# MAX31865ATP.net
KiCad netlist of a schematic drawn in Altium Designer
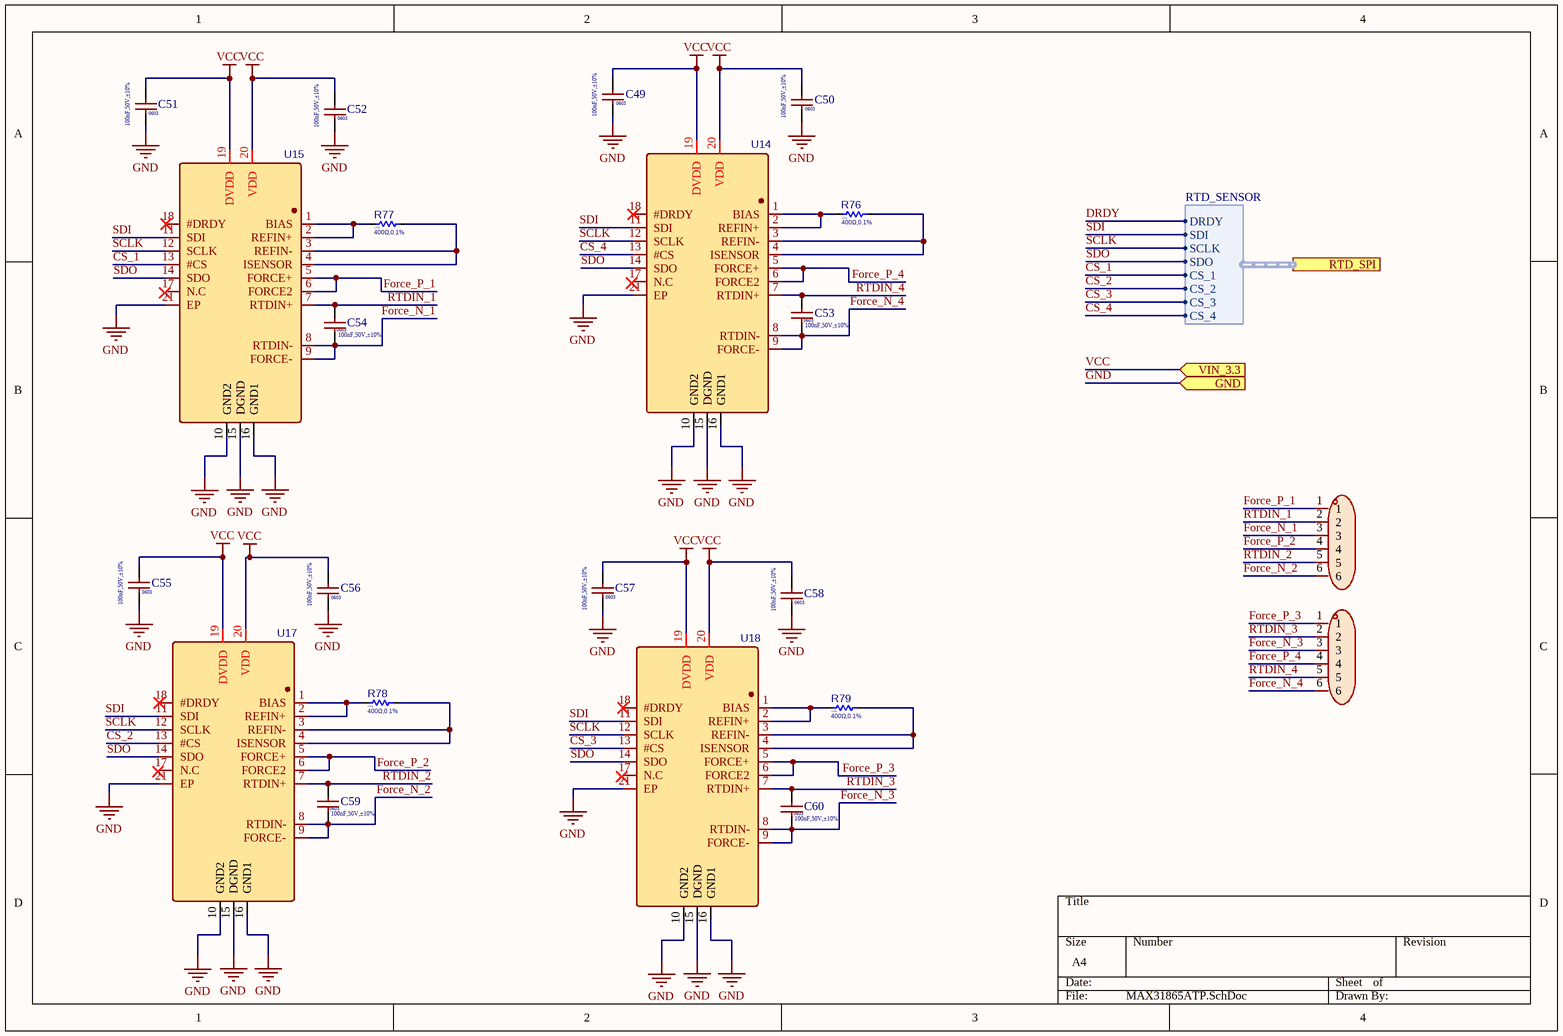
[diagram p0: MAX31865ATP.SchDoc]

(export (version "E")
  (design (tool "Eeschema 10.0.6"))
  (components
    (comp (ref "C49")
      (value "100nF,50V,±10%")
      (footprint "RCL:C0603")
      (description "50V 100nF X7R ±10% 0603 Multilayer Ceramic Capacitors MLCC - SMD/SMT ROHS")
      (fields
        (field (name "MPN") "CL10B104KB8NNNC")
        (field (name "MANUFACTURER") "SAMSUNG")
        (field (name "PACKAGE") "0603")
      )
      (libsource (lib "RCL") (part "CL10B104KB8NNNC"))
    )
    (comp (ref "C50")
      (value "100nF,50V,±10%")
      (footprint "RCL:C0603")
      (description "50V 100nF X7R ±10% 0603 Multilayer Ceramic Capacitors MLCC - SMD/SMT ROHS")
      (fields
        (field (name "MPN") "CL10B104KB8NNNC")
        (field (name "MANUFACTURER") "SAMSUNG")
        (field (name "PACKAGE") "0603")
      )
      (libsource (lib "RCL") (part "CL10B104KB8NNNC"))
    )
    (comp (ref "C51")
      (value "100nF,50V,±10%")
      (footprint "RCL:C0603")
      (description "50V 100nF X7R ±10% 0603 Multilayer Ceramic Capacitors MLCC - SMD/SMT ROHS")
      (fields
        (field (name "MPN") "CL10B104KB8NNNC")
        (field (name "MANUFACTURER") "SAMSUNG")
        (field (name "PACKAGE") "0603")
      )
      (libsource (lib "RCL") (part "CL10B104KB8NNNC"))
    )
    (comp (ref "C52")
      (value "100nF,50V,±10%")
      (footprint "RCL:C0603")
      (description "50V 100nF X7R ±10% 0603 Multilayer Ceramic Capacitors MLCC - SMD/SMT ROHS")
      (fields
        (field (name "MPN") "CL10B104KB8NNNC")
        (field (name "MANUFACTURER") "SAMSUNG")
        (field (name "PACKAGE") "0603")
      )
      (libsource (lib "RCL") (part "CL10B104KB8NNNC"))
    )
    (comp (ref "C53")
      (value "100nF,50V,±10%")
      (footprint "RCL:C0603")
      (description "50V 100nF X7R ±10% 0603 Multilayer Ceramic Capacitors MLCC - SMD/SMT ROHS")
      (fields
        (field (name "MPN") "CL10B104KB8NNNC")
        (field (name "MANUFACTURER") "SAMSUNG")
        (field (name "PACKAGE") "0603")
      )
      (libsource (lib "RCL") (part "CL10B104KB8NNNC"))
    )
    (comp (ref "C54")
      (value "100nF,50V,±10%")
      (footprint "RCL:C0603")
      (description "50V 100nF X7R ±10% 0603 Multilayer Ceramic Capacitors MLCC - SMD/SMT ROHS")
      (fields
        (field (name "MPN") "CL10B104KB8NNNC")
        (field (name "MANUFACTURER") "SAMSUNG")
        (field (name "PACKAGE") "0603")
      )
      (libsource (lib "RCL") (part "CL10B104KB8NNNC"))
    )
    (comp (ref "C55")
      (value "100nF,50V,±10%")
      (footprint "RCL:C0603")
      (description "50V 100nF X7R ±10% 0603 Multilayer Ceramic Capacitors MLCC - SMD/SMT ROHS")
      (fields
        (field (name "MPN") "CL10B104KB8NNNC")
        (field (name "MANUFACTURER") "SAMSUNG")
        (field (name "PACKAGE") "0603")
      )
      (libsource (lib "RCL") (part "CL10B104KB8NNNC"))
    )
    (comp (ref "C56")
      (value "100nF,50V,±10%")
      (footprint "RCL:C0603")
      (description "50V 100nF X7R ±10% 0603 Multilayer Ceramic Capacitors MLCC - SMD/SMT ROHS")
      (fields
        (field (name "MPN") "CL10B104KB8NNNC")
        (field (name "MANUFACTURER") "SAMSUNG")
        (field (name "PACKAGE") "0603")
      )
      (libsource (lib "RCL") (part "CL10B104KB8NNNC"))
    )
    (comp (ref "C57")
      (value "100nF,50V,±10%")
      (footprint "RCL:C0603")
      (description "50V 100nF X7R ±10% 0603 Multilayer Ceramic Capacitors MLCC - SMD/SMT ROHS")
      (fields
        (field (name "MPN") "CL10B104KB8NNNC")
        (field (name "MANUFACTURER") "SAMSUNG")
        (field (name "PACKAGE") "0603")
      )
      (libsource (lib "RCL") (part "CL10B104KB8NNNC"))
    )
    (comp (ref "C58")
      (value "100nF,50V,±10%")
      (footprint "RCL:C0603")
      (description "50V 100nF X7R ±10% 0603 Multilayer Ceramic Capacitors MLCC - SMD/SMT ROHS")
      (fields
        (field (name "MPN") "CL10B104KB8NNNC")
        (field (name "MANUFACTURER") "SAMSUNG")
        (field (name "PACKAGE") "0603")
      )
      (libsource (lib "RCL") (part "CL10B104KB8NNNC"))
    )
    (comp (ref "C59")
      (value "100nF,50V,±10%")
      (footprint "RCL:C0603")
      (description "50V 100nF X7R ±10% 0603 Multilayer Ceramic Capacitors MLCC - SMD/SMT ROHS")
      (fields
        (field (name "MPN") "CL10B104KB8NNNC")
        (field (name "MANUFACTURER") "SAMSUNG")
        (field (name "PACKAGE") "0603")
      )
      (libsource (lib "RCL") (part "CL10B104KB8NNNC"))
    )
    (comp (ref "C60")
      (value "100nF,50V,±10%")
      (footprint "RCL:C0603")
      (description "50V 100nF X7R ±10% 0603 Multilayer Ceramic Capacitors MLCC - SMD/SMT ROHS")
      (fields
        (field (name "MPN") "CL10B104KB8NNNC")
        (field (name "MANUFACTURER") "SAMSUNG")
        (field (name "PACKAGE") "0603")
      )
      (libsource (lib "RCL") (part "CL10B104KB8NNNC"))
    )
    (comp (ref "R76")
      (value "400Ω,0.1%")
      (footprint "R1206")
      (description "250mW Thin Film Resistor 200V ±25ppm/℃ ±0.1% 400Ω 1206 Chip Resistor - Surface Mount ROHS")
      (fields
        (field (name "MANUFACTURER") "YAGEO")
        (field (name "MPN") "RT1206BRD07400RL")
        (field (name "PACKAGE") "1206")
      )
      (libsource (lib "RCL") (part "RT1206BRD07400RL"))
    )
    (comp (ref "R77")
      (value "400Ω,0.1%")
      (footprint "R1206")
      (description "250mW Thin Film Resistor 200V ±25ppm/℃ ±0.1% 400Ω 1206 Chip Resistor - Surface Mount ROHS")
      (fields
        (field (name "MANUFACTURER") "YAGEO")
        (field (name "MPN") "RT1206BRD07400RL")
        (field (name "PACKAGE") "1206")
      )
      (libsource (lib "RCL") (part "RT1206BRD07400RL"))
    )
    (comp (ref "R78")
      (value "400Ω,0.1%")
      (footprint "R1206")
      (description "250mW Thin Film Resistor 200V ±25ppm/℃ ±0.1% 400Ω 1206 Chip Resistor - Surface Mount ROHS")
      (fields
        (field (name "MANUFACTURER") "YAGEO")
        (field (name "MPN") "RT1206BRD07400RL")
        (field (name "PACKAGE") "1206")
      )
      (libsource (lib "RCL") (part "RT1206BRD07400RL"))
    )
    (comp (ref "R79")
      (value "400Ω,0.1%")
      (footprint "R1206")
      (description "250mW Thin Film Resistor 200V ±25ppm/℃ ±0.1% 400Ω 1206 Chip Resistor - Surface Mount ROHS")
      (fields
        (field (name "MANUFACTURER") "YAGEO")
        (field (name "MPN") "RT1206BRD07400RL")
        (field (name "PACKAGE") "1206")
      )
      (libsource (lib "RCL") (part "RT1206BRD07400RL"))
    )
    (comp (ref "U14")
      (value "MAX31865ATP+T")
      (footprint "QFN-20-EP(5x5)")
      (description "QFN-20-EP(5x5) Analog to Digital Converters (ADC) ROHS")
      (fields (field (name "MANUFACTURER") "ADI/MAXIM"))
      (libsource (lib "IC") (part "MAX31865ATP+T"))
    )
    (comp (ref "U15")
      (value "MAX31865ATP+T")
      (footprint "QFN-20-EP(5x5)")
      (description "QFN-20-EP(5x5) Analog to Digital Converters (ADC) ROHS")
      (fields (field (name "MANUFACTURER") "ADI/MAXIM"))
      (libsource (lib "IC") (part "MAX31865ATP+T"))
    )
    (comp (ref "U16")
      (value "DBT50G-6.35-6P-BK-P OGC")
      (footprint "6P_P=6.35mm")
      (fields (field (name "MANUFACTURER") "DORABO(地博电气)"))
      (libsource (lib "connector_button") (part "DBT50G-6.35-6P-BK-P OGC"))
    )
    (comp (ref "U17")
      (value "MAX31865ATP+T")
      (footprint "QFN-20-EP(5x5)")
      (description "QFN-20-EP(5x5) Analog to Digital Converters (ADC) ROHS")
      (fields (field (name "MANUFACTURER") "ADI/MAXIM"))
      (libsource (lib "IC") (part "MAX31865ATP+T"))
    )
    (comp (ref "U18")
      (value "MAX31865ATP+T")
      (footprint "QFN-20-EP(5x5)")
      (description "QFN-20-EP(5x5) Analog to Digital Converters (ADC) ROHS")
      (fields (field (name "MANUFACTURER") "ADI/MAXIM"))
      (libsource (lib "IC") (part "MAX31865ATP+T"))
    )
    (comp (ref "U19")
      (value "DBT50G-6.35-6P-BK-P OGC")
      (footprint "6P_P=6.35mm")
      (fields (field (name "MANUFACTURER") "DORABO(地博电气)"))
      (libsource (lib "connector_button") (part "DBT50G-6.35-6P-BK-P OGC"))
    )
  )
  (nets
    (net (code "2") (name "/CS_1") (class "Default")
      (node (ref "U15") (pin "13") (pinfunction "#CS_13") (pintype "passive"))
    )
    (net (code "3") (name "/CS_2") (class "Default")
      (node (ref "U17") (pin "13") (pinfunction "#CS_13") (pintype "passive"))
    )
    (net (code "4") (name "/CS_3") (class "Default")
      (node (ref "U18") (pin "13") (pinfunction "#CS_13") (pintype "passive"))
    )
    (net (code "5") (name "/CS_4") (class "Default")
      (node (ref "U14") (pin "13") (pinfunction "#CS_13") (pintype "passive"))
    )
    (net (code "7") (name "/Force_N_1") (class "Default")
      (node (ref "C54") (pin "2") (pinfunction "2_2") (pintype "passive"))
      (node (ref "U15") (pin "8") (pinfunction "RTDIN-_8") (pintype "passive"))
      (node (ref "U15") (pin "9") (pinfunction "FORCE-_9") (pintype "passive"))
      (node (ref "U16") (pin "3") (pinfunction "3_3") (pintype "passive"))
    )
    (net (code "8") (name "/Force_N_2") (class "Default")
      (node (ref "C59") (pin "2") (pinfunction "2_2") (pintype "passive"))
      (node (ref "U16") (pin "6") (pinfunction "6_6") (pintype "passive"))
      (node (ref "U17") (pin "8") (pinfunction "RTDIN-_8") (pintype "passive"))
      (node (ref "U17") (pin "9") (pinfunction "FORCE-_9") (pintype "passive"))
    )
    (net (code "9") (name "/Force_N_3") (class "Default")
      (node (ref "C60") (pin "2") (pinfunction "2_2") (pintype "passive"))
      (node (ref "U18") (pin "8") (pinfunction "RTDIN-_8") (pintype "passive"))
      (node (ref "U18") (pin "9") (pinfunction "FORCE-_9") (pintype "passive"))
      (node (ref "U19") (pin "3") (pinfunction "3_3") (pintype "passive"))
    )
    (net (code "10") (name "/Force_N_4") (class "Default")
      (node (ref "C53") (pin "2") (pinfunction "2_2") (pintype "passive"))
      (node (ref "U14") (pin "8") (pinfunction "RTDIN-_8") (pintype "passive"))
      (node (ref "U14") (pin "9") (pinfunction "FORCE-_9") (pintype "passive"))
      (node (ref "U19") (pin "6") (pinfunction "6_6") (pintype "passive"))
    )
    (net (code "11") (name "/Force_P_1") (class "Default")
      (node (ref "U15") (pin "5") (pinfunction "FORCE+_5") (pintype "passive"))
      (node (ref "U15") (pin "6") (pinfunction "FORCE2_6") (pintype "passive"))
      (node (ref "U16") (pin "1") (pinfunction "1_1") (pintype "passive"))
    )
    (net (code "12") (name "/Force_P_2") (class "Default")
      (node (ref "U16") (pin "4") (pinfunction "4_4") (pintype "passive"))
      (node (ref "U17") (pin "5") (pinfunction "FORCE+_5") (pintype "passive"))
      (node (ref "U17") (pin "6") (pinfunction "FORCE2_6") (pintype "passive"))
    )
    (net (code "13") (name "/Force_P_3") (class "Default")
      (node (ref "U18") (pin "5") (pinfunction "FORCE+_5") (pintype "passive"))
      (node (ref "U18") (pin "6") (pinfunction "FORCE2_6") (pintype "passive"))
      (node (ref "U19") (pin "1") (pinfunction "1_1") (pintype "passive"))
    )
    (net (code "14") (name "/Force_P_4") (class "Default")
      (node (ref "U14") (pin "5") (pinfunction "FORCE+_5") (pintype "passive"))
      (node (ref "U14") (pin "6") (pinfunction "FORCE2_6") (pintype "passive"))
      (node (ref "U19") (pin "4") (pinfunction "4_4") (pintype "passive"))
    )
    (net (code "15") (name "/RTDIN_1") (class "Default")
      (node (ref "C54") (pin "1") (pinfunction "1_1") (pintype "passive"))
      (node (ref "U15") (pin "7") (pinfunction "RTDIN+_7") (pintype "passive"))
      (node (ref "U16") (pin "2") (pinfunction "2_2") (pintype "passive"))
    )
    (net (code "16") (name "/RTDIN_2") (class "Default")
      (node (ref "C59") (pin "1") (pinfunction "1_1") (pintype "passive"))
      (node (ref "U16") (pin "5") (pinfunction "5_5") (pintype "passive"))
      (node (ref "U17") (pin "7") (pinfunction "RTDIN+_7") (pintype "passive"))
    )
    (net (code "17") (name "/RTDIN_3") (class "Default")
      (node (ref "C60") (pin "1") (pinfunction "1_1") (pintype "passive"))
      (node (ref "U18") (pin "7") (pinfunction "RTDIN+_7") (pintype "passive"))
      (node (ref "U19") (pin "2") (pinfunction "2_2") (pintype "passive"))
    )
    (net (code "18") (name "/RTDIN_4") (class "Default")
      (node (ref "C53") (pin "1") (pinfunction "1_1") (pintype "passive"))
      (node (ref "U14") (pin "7") (pinfunction "RTDIN+_7") (pintype "passive"))
      (node (ref "U19") (pin "5") (pinfunction "5_5") (pintype "passive"))
    )
    (net (code "19") (name "/SCLK") (class "Default")
      (node (ref "U14") (pin "12") (pinfunction "SCLK_12") (pintype "passive"))
      (node (ref "U15") (pin "12") (pinfunction "SCLK_12") (pintype "passive"))
      (node (ref "U17") (pin "12") (pinfunction "SCLK_12") (pintype "passive"))
      (node (ref "U18") (pin "12") (pinfunction "SCLK_12") (pintype "passive"))
    )
    (net (code "20") (name "/SDI") (class "Default")
      (node (ref "U14") (pin "11") (pinfunction "SDI_11") (pintype "passive"))
      (node (ref "U15") (pin "11") (pinfunction "SDI_11") (pintype "passive"))
      (node (ref "U17") (pin "11") (pinfunction "SDI_11") (pintype "passive"))
      (node (ref "U18") (pin "11") (pinfunction "SDI_11") (pintype "passive"))
    )
    (net (code "21") (name "/SDO") (class "Default")
      (node (ref "U14") (pin "14") (pinfunction "SDO_14") (pintype "passive"))
      (node (ref "U15") (pin "14") (pinfunction "SDO_14") (pintype "passive"))
      (node (ref "U17") (pin "14") (pinfunction "SDO_14") (pintype "passive"))
      (node (ref "U18") (pin "14") (pinfunction "SDO_14") (pintype "passive"))
    )
    (net (code "23") (name "GND") (class "Default")
      (node (ref "C49") (pin "1") (pinfunction "1_1") (pintype "passive"))
      (node (ref "C50") (pin "1") (pinfunction "1_1") (pintype "passive"))
      (node (ref "C51") (pin "1") (pinfunction "1_1") (pintype "passive"))
      (node (ref "C52") (pin "1") (pinfunction "1_1") (pintype "passive"))
      (node (ref "C55") (pin "1") (pinfunction "1_1") (pintype "passive"))
      (node (ref "C56") (pin "1") (pinfunction "1_1") (pintype "passive"))
      (node (ref "C57") (pin "1") (pinfunction "1_1") (pintype "passive"))
      (node (ref "C58") (pin "1") (pinfunction "1_1") (pintype "passive"))
      (node (ref "U14") (pin "10") (pinfunction "GND2_10") (pintype "passive"))
      (node (ref "U14") (pin "15") (pinfunction "DGND_15") (pintype "passive"))
      (node (ref "U14") (pin "16") (pinfunction "GND1_16") (pintype "passive"))
      (node (ref "U14") (pin "21") (pinfunction "EP_21") (pintype "passive"))
      (node (ref "U15") (pin "10") (pinfunction "GND2_10") (pintype "passive"))
      (node (ref "U15") (pin "15") (pinfunction "DGND_15") (pintype "passive"))
      (node (ref "U15") (pin "16") (pinfunction "GND1_16") (pintype "passive"))
      (node (ref "U15") (pin "21") (pinfunction "EP_21") (pintype "passive"))
      (node (ref "U17") (pin "10") (pinfunction "GND2_10") (pintype "passive"))
      (node (ref "U17") (pin "15") (pinfunction "DGND_15") (pintype "passive"))
      (node (ref "U17") (pin "16") (pinfunction "GND1_16") (pintype "passive"))
      (node (ref "U17") (pin "21") (pinfunction "EP_21") (pintype "passive"))
      (node (ref "U18") (pin "10") (pinfunction "GND2_10") (pintype "passive"))
      (node (ref "U18") (pin "15") (pinfunction "DGND_15") (pintype "passive"))
      (node (ref "U18") (pin "16") (pinfunction "GND1_16") (pintype "passive"))
      (node (ref "U18") (pin "21") (pinfunction "EP_21") (pintype "passive"))
    )
    (net (code "24") (name "Net-(U14-BIAS)") (class "Default")
      (node (ref "R76") (pin "2") (pinfunction "2_2") (pintype "passive"))
      (node (ref "U14") (pin "1") (pinfunction "BIAS_1") (pintype "passive"))
      (node (ref "U14") (pin "2") (pinfunction "REFIN+_2") (pintype "passive"))
    )
    (net (code "25") (name "Net-(U14-ISENSOR)") (class "Default")
      (node (ref "R76") (pin "1") (pinfunction "1_1") (pintype "passive"))
      (node (ref "U14") (pin "3") (pinfunction "REFIN-_3") (pintype "passive"))
      (node (ref "U14") (pin "4") (pinfunction "ISENSOR_4") (pintype "passive"))
    )
    (net (code "26") (name "Net-(U15-BIAS)") (class "Default")
      (node (ref "R77") (pin "2") (pinfunction "2_2") (pintype "passive"))
      (node (ref "U15") (pin "1") (pinfunction "BIAS_1") (pintype "passive"))
      (node (ref "U15") (pin "2") (pinfunction "REFIN+_2") (pintype "passive"))
    )
    (net (code "27") (name "Net-(U15-ISENSOR)") (class "Default")
      (node (ref "R77") (pin "1") (pinfunction "1_1") (pintype "passive"))
      (node (ref "U15") (pin "3") (pinfunction "REFIN-_3") (pintype "passive"))
      (node (ref "U15") (pin "4") (pinfunction "ISENSOR_4") (pintype "passive"))
    )
    (net (code "28") (name "Net-(U17-BIAS)") (class "Default")
      (node (ref "R78") (pin "2") (pinfunction "2_2") (pintype "passive"))
      (node (ref "U17") (pin "1") (pinfunction "BIAS_1") (pintype "passive"))
      (node (ref "U17") (pin "2") (pinfunction "REFIN+_2") (pintype "passive"))
    )
    (net (code "29") (name "Net-(U17-ISENSOR)") (class "Default")
      (node (ref "R78") (pin "1") (pinfunction "1_1") (pintype "passive"))
      (node (ref "U17") (pin "3") (pinfunction "REFIN-_3") (pintype "passive"))
      (node (ref "U17") (pin "4") (pinfunction "ISENSOR_4") (pintype "passive"))
    )
    (net (code "30") (name "Net-(U18-BIAS)") (class "Default")
      (node (ref "R79") (pin "2") (pinfunction "2_2") (pintype "passive"))
      (node (ref "U18") (pin "1") (pinfunction "BIAS_1") (pintype "passive"))
      (node (ref "U18") (pin "2") (pinfunction "REFIN+_2") (pintype "passive"))
    )
    (net (code "31") (name "Net-(U18-ISENSOR)") (class "Default")
      (node (ref "R79") (pin "1") (pinfunction "1_1") (pintype "passive"))
      (node (ref "U18") (pin "3") (pinfunction "REFIN-_3") (pintype "passive"))
      (node (ref "U18") (pin "4") (pinfunction "ISENSOR_4") (pintype "passive"))
    )
    (net (code "32") (name "VCC") (class "Default")
      (node (ref "C49") (pin "2") (pinfunction "2_2") (pintype "passive"))
      (node (ref "C50") (pin "2") (pinfunction "2_2") (pintype "passive"))
      (node (ref "C51") (pin "2") (pinfunction "2_2") (pintype "passive"))
      (node (ref "C52") (pin "2") (pinfunction "2_2") (pintype "passive"))
      (node (ref "C55") (pin "2") (pinfunction "2_2") (pintype "passive"))
      (node (ref "C56") (pin "2") (pinfunction "2_2") (pintype "passive"))
      (node (ref "C57") (pin "2") (pinfunction "2_2") (pintype "passive"))
      (node (ref "C58") (pin "2") (pinfunction "2_2") (pintype "passive"))
      (node (ref "U14") (pin "19") (pinfunction "DVDD_19") (pintype "passive"))
      (node (ref "U14") (pin "20") (pinfunction "VDD_20") (pintype "passive"))
      (node (ref "U15") (pin "19") (pinfunction "DVDD_19") (pintype "passive"))
      (node (ref "U15") (pin "20") (pinfunction "VDD_20") (pintype "passive"))
      (node (ref "U17") (pin "19") (pinfunction "DVDD_19") (pintype "passive"))
      (node (ref "U17") (pin "20") (pinfunction "VDD_20") (pintype "passive"))
      (node (ref "U18") (pin "19") (pinfunction "DVDD_19") (pintype "passive"))
      (node (ref "U18") (pin "20") (pinfunction "VDD_20") (pintype "passive"))
    )
    (net (code "33") (name "unconnected-(U14-#DRDY-Pad18)") (class "Default")
      (node (ref "U14") (pin "18") (pinfunction "#DRDY_18") (pintype "passive+no_connect"))
    )
    (net (code "34") (name "unconnected-(U14-N.C-Pad17)") (class "Default")
      (node (ref "U14") (pin "17") (pinfunction "N.C_17") (pintype "passive"))
    )
    (net (code "35") (name "unconnected-(U15-#DRDY-Pad18)") (class "Default")
      (node (ref "U15") (pin "18") (pinfunction "#DRDY_18") (pintype "passive+no_connect"))
    )
    (net (code "36") (name "unconnected-(U15-N.C-Pad17)") (class "Default")
      (node (ref "U15") (pin "17") (pinfunction "N.C_17") (pintype "passive"))
    )
    (net (code "37") (name "unconnected-(U17-#DRDY-Pad18)") (class "Default")
      (node (ref "U17") (pin "18") (pinfunction "#DRDY_18") (pintype "passive+no_connect"))
    )
    (net (code "38") (name "unconnected-(U17-N.C-Pad17)") (class "Default")
      (node (ref "U17") (pin "17") (pinfunction "N.C_17") (pintype "passive"))
    )
    (net (code "39") (name "unconnected-(U18-#DRDY-Pad18)") (class "Default")
      (node (ref "U18") (pin "18") (pinfunction "#DRDY_18") (pintype "passive+no_connect"))
    )
    (net (code "40") (name "unconnected-(U18-N.C-Pad17)") (class "Default")
      (node (ref "U18") (pin "17") (pinfunction "N.C_17") (pintype "passive"))
    )
  )
)
